# Codeshelf-0007_v02.net
KiCad netlist of a schematic drawn in EAGLE
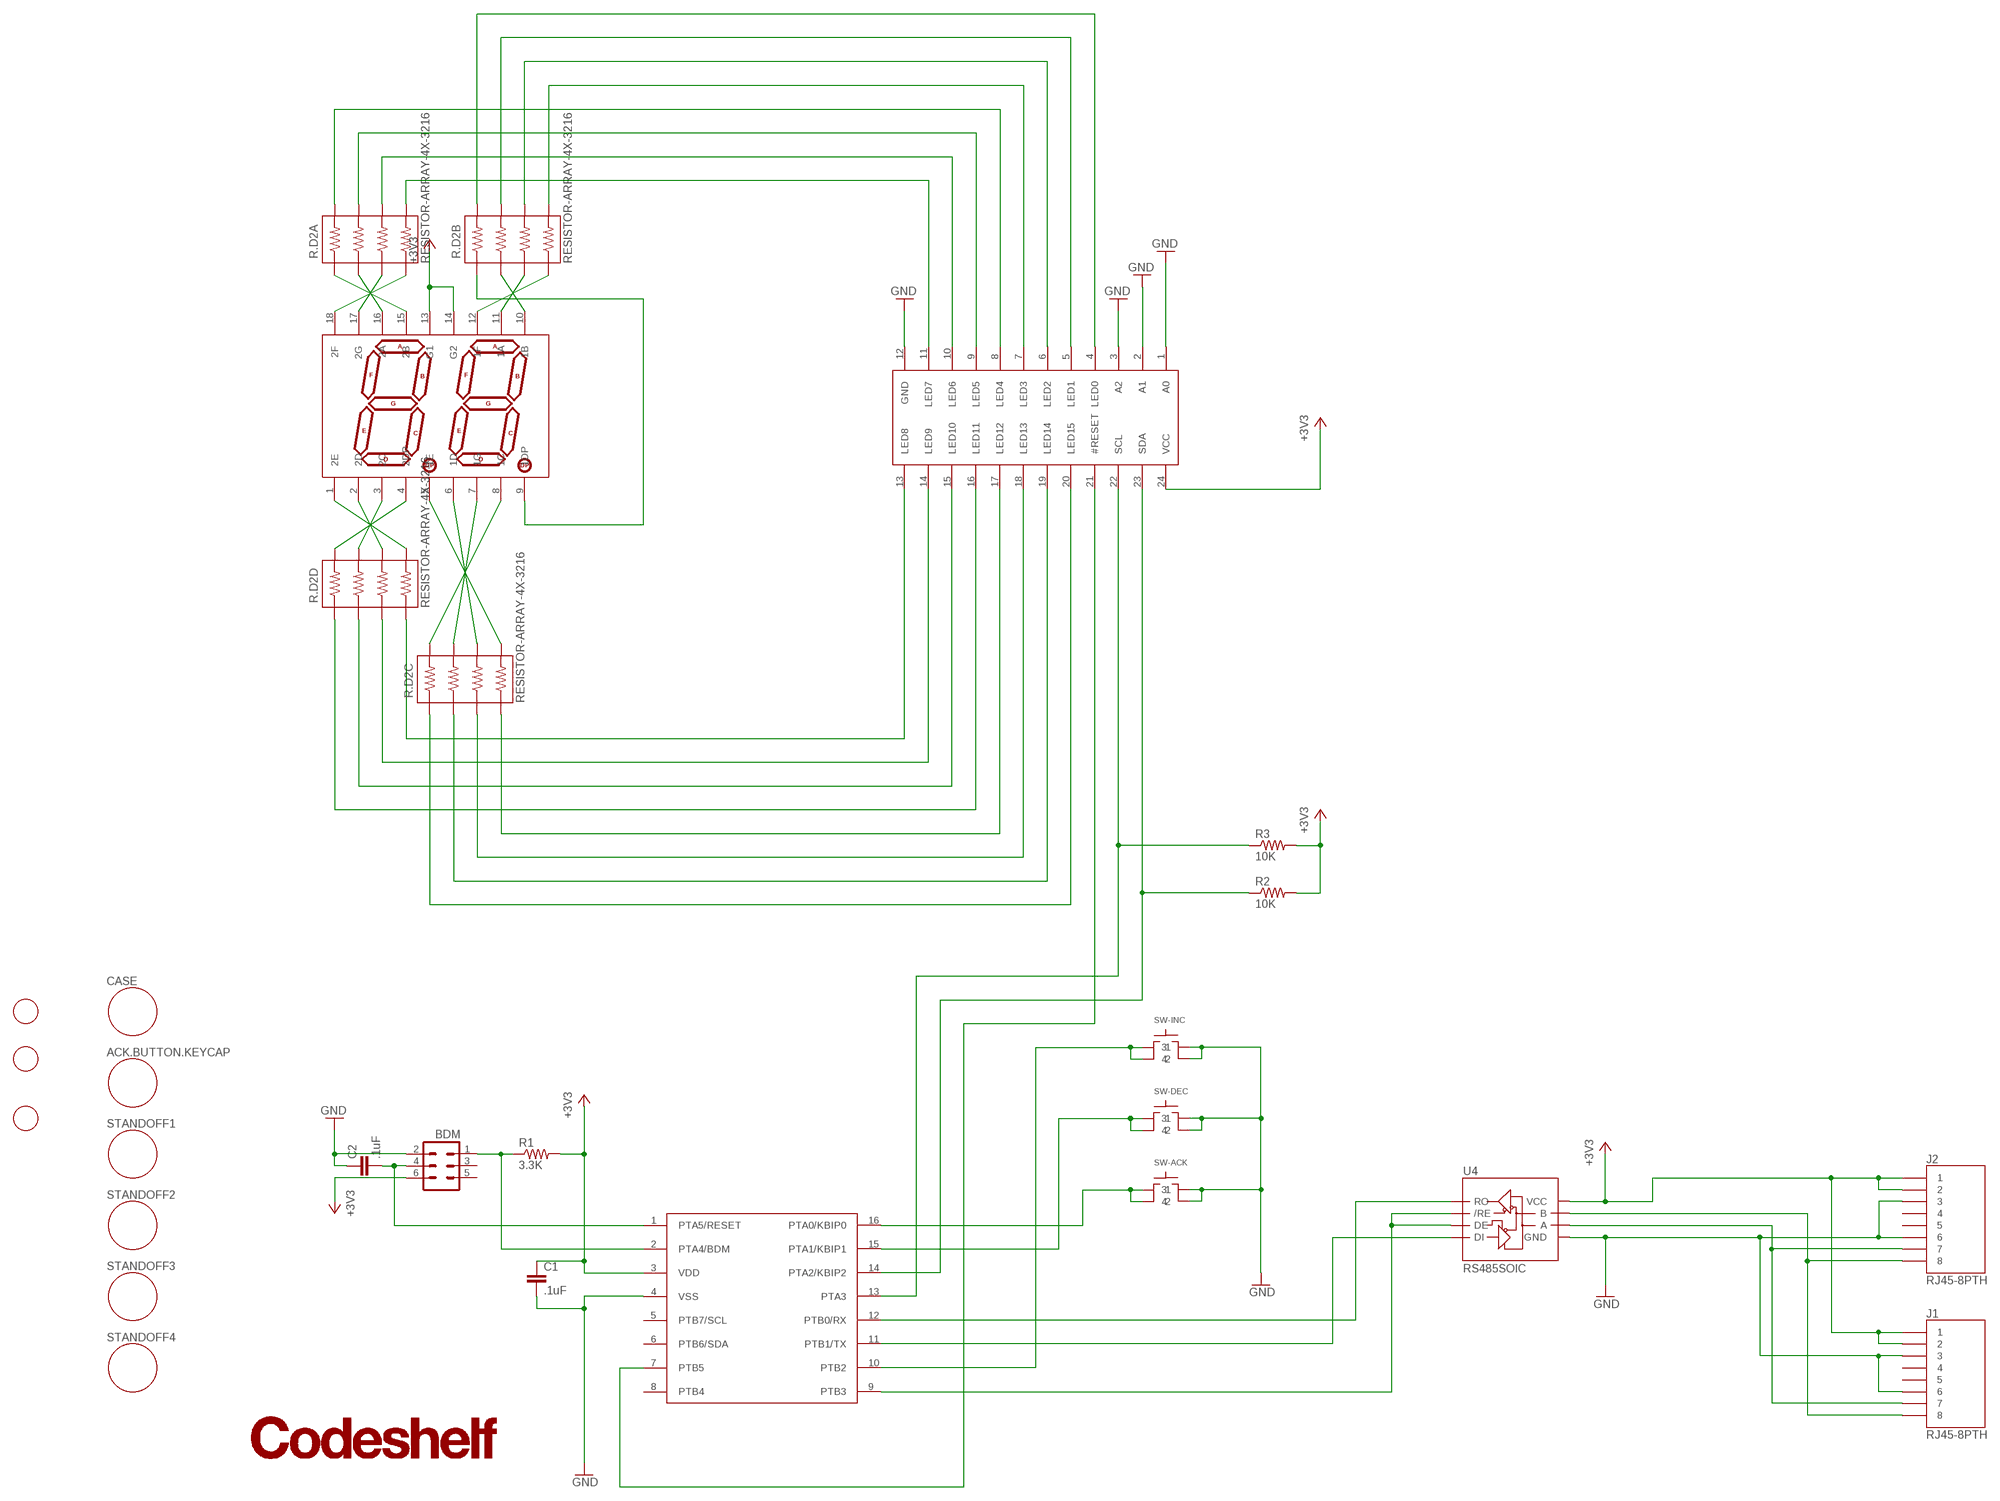
[diagram p0: schematic, sheet 1]

(export (version "E")
  (design (tool "Eeschema 10.0.6"))
  (components
    (comp (ref "ACK.BUTTON.KEYCAP")
      (value "EXTERNAL-COMPONENT")
      (footprint "eagle-import:EXTERNAL-COMPONENT")
      (libsource (lib "eagle-import") (part "EXTERNAL-COMPONENT"))
    )
    (comp (ref "BDM")
      (value "HEADER-3X2")
      (footprint "eagle-import:HEADER-3X2")
      (libsource (lib "eagle-import") (part "HEADER-3X2"))
    )
    (comp (ref "C1")
      (value ".1uF")
      (footprint "eagle-import:C0402")
      (libsource (lib "eagle-import") (part "RF-C0402"))
    )
    (comp (ref "C2")
      (value ".1uF")
      (footprint "eagle-import:C0402")
      (libsource (lib "eagle-import") (part "RF-C0402"))
    )
    (comp (ref "CASE")
      (value "EXTERNAL-COMPONENT")
      (footprint "eagle-import:EXTERNAL-COMPONENT")
      (libsource (lib "eagle-import") (part "EXTERNAL-COMPONENT"))
    )
    (comp (ref "J1")
      (value "RJ45-8PTH")
      (footprint "eagle-import:RJ45-8")
      (libsource (lib "eagle-import") (part "RJ45-8PTH"))
    )
    (comp (ref "J2")
      (value "RJ45-8PTH")
      (footprint "eagle-import:RJ45-8")
      (libsource (lib "eagle-import") (part "RJ45-8PTH"))
    )
    (comp (ref "LOGO")
      (value "CODESHELF-LOGO")
      (footprint "eagle-import:CODESHELF-LOGO")
      (libsource (lib "eagle-import") (part "CODESHELF-LOGO"))
    )
    (comp (ref "R.D2A")
      (value "RESISTOR-ARRAY-4X-3216")
      (footprint "eagle-import:3216-4X")
      (libsource (lib "eagle-import") (part "RESISTOR-ARRAY-4X-3216"))
    )
    (comp (ref "R.D2B")
      (value "RESISTOR-ARRAY-4X-3216")
      (footprint "eagle-import:3216-4X")
      (libsource (lib "eagle-import") (part "RESISTOR-ARRAY-4X-3216"))
    )
    (comp (ref "R.D2C")
      (value "RESISTOR-ARRAY-4X-3216")
      (footprint "eagle-import:3216-4X")
      (libsource (lib "eagle-import") (part "RESISTOR-ARRAY-4X-3216"))
    )
    (comp (ref "R.D2D")
      (value "RESISTOR-ARRAY-4X-3216")
      (footprint "eagle-import:3216-4X")
      (libsource (lib "eagle-import") (part "RESISTOR-ARRAY-4X-3216"))
    )
    (comp (ref "R1")
      (value "3.3K")
      (footprint "eagle-import:RF-R0402")
      (libsource (lib "eagle-import") (part "RF-R0402"))
    )
    (comp (ref "R2")
      (value "10K")
      (footprint "eagle-import:RF-R0402")
      (libsource (lib "eagle-import") (part "RF-R0402"))
    )
    (comp (ref "R3")
      (value "10K")
      (footprint "eagle-import:RF-R0402")
      (libsource (lib "eagle-import") (part "RF-R0402"))
    )
    (comp (ref "STANDOFF1")
      (value "EXTERNAL-COMPONENT")
      (footprint "eagle-import:EXTERNAL-COMPONENT")
      (libsource (lib "eagle-import") (part "EXTERNAL-COMPONENT"))
    )
    (comp (ref "STANDOFF2")
      (value "EXTERNAL-COMPONENT")
      (footprint "eagle-import:EXTERNAL-COMPONENT")
      (libsource (lib "eagle-import") (part "EXTERNAL-COMPONENT"))
    )
    (comp (ref "STANDOFF3")
      (value "EXTERNAL-COMPONENT")
      (footprint "eagle-import:EXTERNAL-COMPONENT")
      (libsource (lib "eagle-import") (part "EXTERNAL-COMPONENT"))
    )
    (comp (ref "STANDOFF4")
      (value "EXTERNAL-COMPONENT")
      (footprint "eagle-import:EXTERNAL-COMPONENT")
      (libsource (lib "eagle-import") (part "EXTERNAL-COMPONENT"))
    )
    (comp (ref "SW-ACK")
      (value "SWITCH-TACTILE-320.03E11")
      (footprint "eagle-import:SWITCH-TACTILE-320.03E11")
      (libsource (lib "eagle-import") (part "SWITCH-TACTILE-320.03E11"))
    )
    (comp (ref "SW-DEC")
      (value "SWITCH-TACTILE-FSM")
      (footprint "eagle-import:SWITCH-TACTILE-FSM")
      (libsource (lib "eagle-import") (part "SWITCH-TACTILE-FSM"))
    )
    (comp (ref "SW-INC")
      (value "SWITCH-TACTILE-FSM")
      (footprint "eagle-import:SWITCH-TACTILE-FSM")
      (libsource (lib "eagle-import") (part "SWITCH-TACTILE-FSM"))
    )
    (comp (ref "U$1")
      (value "FIDUCIAL")
      (footprint "eagle-import:FIDUCIAL_1MM")
      (libsource (lib "eagle-import") (part "FIDUCIAL"))
    )
    (comp (ref "U$2")
      (value "FIDUCIAL")
      (footprint "eagle-import:FIDUCIAL_1MM")
      (libsource (lib "eagle-import") (part "FIDUCIAL"))
    )
    (comp (ref "U$3")
      (value "FIDUCIAL")
      (footprint "eagle-import:FIDUCIAL_1MM")
      (libsource (lib "eagle-import") (part "FIDUCIAL"))
    )
    (comp (ref "U2")
      (value "MC9S08QG-DT")
      (footprint "eagle-import:TSSOP16")
      (libsource (lib "eagle-import") (part "MC9S08QG-DT"))
    )
    (comp (ref "U3")
      (value "CAT9552")
      (footprint "eagle-import:TSSOP24")
      (libsource (lib "eagle-import") (part "CAT9552"))
    )
    (comp (ref "U4")
      (value "RS485SOIC")
      (footprint "eagle-import:SO08")
      (libsource (lib "eagle-import") (part "RS485SOIC"))
    )
    (comp (ref "U7")
      (value "7SEGMENT-2DIGIT")
      (footprint "eagle-import:7SEGMENT-2DIG-.54")
      (libsource (lib "eagle-import") (part "7SEGMENT-2DIGIT"))
    )
  )
  (nets
    (net (code "1") (name "+3V3") (class "Default")
      (node (ref "BDM") (pin "6") (pinfunction "6_6") (pintype "passive"))
      (node (ref "C1") (pin "1") (pinfunction "1_1") (pintype "passive"))
      (node (ref "J1") (pin "1") (pinfunction "1_1") (pintype "bidirectional"))
      (node (ref "J1") (pin "2") (pinfunction "2_2") (pintype "bidirectional"))
      (node (ref "J2") (pin "1") (pinfunction "1_1") (pintype "bidirectional"))
      (node (ref "J2") (pin "2") (pinfunction "2_2") (pintype "bidirectional"))
      (node (ref "R1") (pin "2") (pinfunction "2_2") (pintype "passive"))
      (node (ref "R2") (pin "2") (pinfunction "2_2") (pintype "passive"))
      (node (ref "R3") (pin "2") (pinfunction "2_2") (pintype "passive"))
      (node (ref "U2") (pin "3") (pinfunction "VDD_3") (pintype "bidirectional"))
      (node (ref "U3") (pin "24") (pinfunction "VCC_24") (pintype "bidirectional"))
      (node (ref "U4") (pin "8") (pinfunction "VCC_8") (pintype "bidirectional"))
      (node (ref "U7") (pin "13") (pinfunction "G1_13") (pintype "bidirectional"))
      (node (ref "U7") (pin "14") (pinfunction "G2_14") (pintype "bidirectional"))
    )
    (net (code "2") (name "GND") (class "Default")
      (node (ref "BDM") (pin "2") (pinfunction "2_2") (pintype "passive"))
      (node (ref "C1") (pin "2") (pinfunction "2_2") (pintype "passive"))
      (node (ref "C2") (pin "1") (pinfunction "1_1") (pintype "passive"))
      (node (ref "J1") (pin "3") (pinfunction "3_3") (pintype "bidirectional"))
      (node (ref "J1") (pin "6") (pinfunction "6_6") (pintype "bidirectional"))
      (node (ref "J2") (pin "3") (pinfunction "3_3") (pintype "bidirectional"))
      (node (ref "J2") (pin "6") (pinfunction "6_6") (pintype "bidirectional"))
      (node (ref "SW-ACK") (pin "P$3") (pinfunction "3_P$3") (pintype "input"))
      (node (ref "SW-ACK") (pin "P$4") (pinfunction "4_P$4") (pintype "input"))
      (node (ref "SW-DEC") (pin "P$3") (pinfunction "3_P$3") (pintype "input"))
      (node (ref "SW-DEC") (pin "P$4") (pinfunction "4_P$4") (pintype "input"))
      (node (ref "SW-INC") (pin "P$3") (pinfunction "3_P$3") (pintype "input"))
      (node (ref "SW-INC") (pin "P$4") (pinfunction "4_P$4") (pintype "input"))
      (node (ref "U2") (pin "4") (pinfunction "VSS_4") (pintype "bidirectional"))
      (node (ref "U3") (pin "1") (pinfunction "A0_1") (pintype "bidirectional"))
      (node (ref "U3") (pin "12") (pinfunction "GND_12") (pintype "bidirectional"))
      (node (ref "U3") (pin "2") (pinfunction "A1_2") (pintype "bidirectional"))
      (node (ref "U3") (pin "3") (pinfunction "A2_3") (pintype "bidirectional"))
      (node (ref "U4") (pin "5") (pinfunction "GND_5") (pintype "bidirectional"))
    )
    (net (code "3") (name "Net-(R.D2A-1A)") (class "Default")
      (node (ref "R.D2A") (pin "1") (pinfunction "1A_1") (pintype "passive"))
      (node (ref "U7") (pin "15") (pinfunction "2B_15") (pintype "bidirectional"))
    )
    (net (code "4") (name "Net-(R.D2A-1B)") (class "Default")
      (node (ref "R.D2A") (pin "8") (pinfunction "1B_8") (pintype "passive"))
      (node (ref "U3") (pin "8") (pinfunction "LED4_8") (pintype "bidirectional"))
    )
    (net (code "5") (name "Net-(R.D2A-2A)") (class "Default")
      (node (ref "R.D2A") (pin "2") (pinfunction "2A_2") (pintype "passive"))
      (node (ref "U7") (pin "16") (pinfunction "2A_16") (pintype "bidirectional"))
    )
    (net (code "6") (name "Net-(R.D2A-2B)") (class "Default")
      (node (ref "R.D2A") (pin "7") (pinfunction "2B_7") (pintype "passive"))
      (node (ref "U3") (pin "9") (pinfunction "LED5_9") (pintype "bidirectional"))
    )
    (net (code "7") (name "Net-(R.D2A-3A)") (class "Default")
      (node (ref "R.D2A") (pin "3") (pinfunction "3A_3") (pintype "passive"))
      (node (ref "U7") (pin "17") (pinfunction "2G_17") (pintype "bidirectional"))
    )
    (net (code "8") (name "Net-(R.D2A-3B)") (class "Default")
      (node (ref "R.D2A") (pin "6") (pinfunction "3B_6") (pintype "passive"))
      (node (ref "U3") (pin "10") (pinfunction "LED6_10") (pintype "bidirectional"))
    )
    (net (code "9") (name "Net-(R.D2A-4A)") (class "Default")
      (node (ref "R.D2A") (pin "4") (pinfunction "4A_4") (pintype "passive"))
      (node (ref "U7") (pin "18") (pinfunction "2F_18") (pintype "bidirectional"))
    )
    (net (code "10") (name "Net-(R.D2A-4B)") (class "Default")
      (node (ref "R.D2A") (pin "5") (pinfunction "4B_5") (pintype "passive"))
      (node (ref "U3") (pin "11") (pinfunction "LED7_11") (pintype "bidirectional"))
    )
    (net (code "11") (name "Net-(R.D2B-1A)") (class "Default")
      (node (ref "R.D2B") (pin "1") (pinfunction "1A_1") (pintype "passive"))
      (node (ref "U7") (pin "9") (pinfunction "1DP_9") (pintype "bidirectional"))
    )
    (net (code "12") (name "Net-(R.D2B-1B)") (class "Default")
      (node (ref "R.D2B") (pin "8") (pinfunction "1B_8") (pintype "passive"))
      (node (ref "U3") (pin "4") (pinfunction "LED0_4") (pintype "bidirectional"))
    )
    (net (code "13") (name "Net-(R.D2B-2A)") (class "Default")
      (node (ref "R.D2B") (pin "2") (pinfunction "2A_2") (pintype "passive"))
      (node (ref "U7") (pin "10") (pinfunction "1B_10") (pintype "bidirectional"))
    )
    (net (code "14") (name "Net-(R.D2B-2B)") (class "Default")
      (node (ref "R.D2B") (pin "7") (pinfunction "2B_7") (pintype "passive"))
      (node (ref "U3") (pin "5") (pinfunction "LED1_5") (pintype "bidirectional"))
    )
    (net (code "15") (name "Net-(R.D2B-3A)") (class "Default")
      (node (ref "R.D2B") (pin "3") (pinfunction "3A_3") (pintype "passive"))
      (node (ref "U7") (pin "11") (pinfunction "1A_11") (pintype "bidirectional"))
    )
    (net (code "16") (name "Net-(R.D2B-3B)") (class "Default")
      (node (ref "R.D2B") (pin "6") (pinfunction "3B_6") (pintype "passive"))
      (node (ref "U3") (pin "6") (pinfunction "LED2_6") (pintype "bidirectional"))
    )
    (net (code "17") (name "Net-(R.D2B-4A)") (class "Default")
      (node (ref "R.D2B") (pin "4") (pinfunction "4A_4") (pintype "passive"))
      (node (ref "U7") (pin "12") (pinfunction "1F_12") (pintype "bidirectional"))
    )
    (net (code "18") (name "Net-(R.D2B-4B)") (class "Default")
      (node (ref "R.D2B") (pin "5") (pinfunction "4B_5") (pintype "passive"))
      (node (ref "U3") (pin "7") (pinfunction "LED3_7") (pintype "bidirectional"))
    )
    (net (code "19") (name "Net-(R.D2C-1A)") (class "Default")
      (node (ref "R.D2C") (pin "1") (pinfunction "1A_1") (pintype "passive"))
      (node (ref "U3") (pin "20") (pinfunction "LED15_20") (pintype "bidirectional"))
    )
    (net (code "20") (name "Net-(R.D2C-1B)") (class "Default")
      (node (ref "R.D2C") (pin "8") (pinfunction "1B_8") (pintype "passive"))
      (node (ref "U7") (pin "8") (pinfunction "1C_8") (pintype "bidirectional"))
    )
    (net (code "21") (name "Net-(R.D2C-2A)") (class "Default")
      (node (ref "R.D2C") (pin "2") (pinfunction "2A_2") (pintype "passive"))
      (node (ref "U3") (pin "19") (pinfunction "LED14_19") (pintype "bidirectional"))
    )
    (net (code "22") (name "Net-(R.D2C-2B)") (class "Default")
      (node (ref "R.D2C") (pin "7") (pinfunction "2B_7") (pintype "passive"))
      (node (ref "U7") (pin "7") (pinfunction "1G_7") (pintype "bidirectional"))
    )
    (net (code "23") (name "Net-(R.D2C-3A)") (class "Default")
      (node (ref "R.D2C") (pin "3") (pinfunction "3A_3") (pintype "passive"))
      (node (ref "U3") (pin "18") (pinfunction "LED13_18") (pintype "bidirectional"))
    )
    (net (code "24") (name "Net-(R.D2C-3B)") (class "Default")
      (node (ref "R.D2C") (pin "6") (pinfunction "3B_6") (pintype "passive"))
      (node (ref "U7") (pin "6") (pinfunction "1D_6") (pintype "bidirectional"))
    )
    (net (code "25") (name "Net-(R.D2C-4A)") (class "Default")
      (node (ref "R.D2C") (pin "4") (pinfunction "4A_4") (pintype "passive"))
      (node (ref "U3") (pin "17") (pinfunction "LED12_17") (pintype "bidirectional"))
    )
    (net (code "26") (name "Net-(R.D2C-4B)") (class "Default")
      (node (ref "R.D2C") (pin "5") (pinfunction "4B_5") (pintype "passive"))
      (node (ref "U7") (pin "5") (pinfunction "1E_5") (pintype "bidirectional"))
    )
    (net (code "27") (name "Net-(R.D2D-1A)") (class "Default")
      (node (ref "R.D2D") (pin "1") (pinfunction "1A_1") (pintype "passive"))
      (node (ref "U3") (pin "16") (pinfunction "LED11_16") (pintype "bidirectional"))
    )
    (net (code "28") (name "Net-(R.D2D-1B)") (class "Default")
      (node (ref "R.D2D") (pin "8") (pinfunction "1B_8") (pintype "passive"))
      (node (ref "U7") (pin "4") (pinfunction "2DP_4") (pintype "bidirectional"))
    )
    (net (code "29") (name "Net-(R.D2D-2A)") (class "Default")
      (node (ref "R.D2D") (pin "2") (pinfunction "2A_2") (pintype "passive"))
      (node (ref "U3") (pin "15") (pinfunction "LED10_15") (pintype "bidirectional"))
    )
    (net (code "30") (name "Net-(R.D2D-2B)") (class "Default")
      (node (ref "R.D2D") (pin "7") (pinfunction "2B_7") (pintype "passive"))
      (node (ref "U7") (pin "3") (pinfunction "2C_3") (pintype "bidirectional"))
    )
    (net (code "31") (name "Net-(R.D2D-3A)") (class "Default")
      (node (ref "R.D2D") (pin "3") (pinfunction "3A_3") (pintype "passive"))
      (node (ref "U3") (pin "14") (pinfunction "LED9_14") (pintype "bidirectional"))
    )
    (net (code "32") (name "Net-(R.D2D-3B)") (class "Default")
      (node (ref "R.D2D") (pin "6") (pinfunction "3B_6") (pintype "passive"))
      (node (ref "U7") (pin "2") (pinfunction "2D_2") (pintype "bidirectional"))
    )
    (net (code "33") (name "Net-(R.D2D-4A)") (class "Default")
      (node (ref "R.D2D") (pin "4") (pinfunction "4A_4") (pintype "passive"))
      (node (ref "U3") (pin "13") (pinfunction "LED8_13") (pintype "bidirectional"))
    )
    (net (code "34") (name "Net-(R.D2D-4B)") (class "Default")
      (node (ref "R.D2D") (pin "5") (pinfunction "4B_5") (pintype "passive"))
      (node (ref "U7") (pin "1") (pinfunction "2E_1") (pintype "bidirectional"))
    )
    (net (code "35") (name "Net-(SW-ACK-1)") (class "Default")
      (node (ref "SW-ACK") (pin "P$1") (pinfunction "1_P$1") (pintype "input"))
      (node (ref "SW-ACK") (pin "P$2") (pinfunction "2_P$2") (pintype "input"))
      (node (ref "U2") (pin "16") (pinfunction "PTA0/KBIP0_16") (pintype "bidirectional"))
    )
    (net (code "36") (name "Net-(SW-DEC-1)") (class "Default")
      (node (ref "SW-DEC") (pin "P$1") (pinfunction "1_P$1") (pintype "input"))
      (node (ref "SW-DEC") (pin "P$2") (pinfunction "2_P$2") (pintype "input"))
      (node (ref "U2") (pin "15") (pinfunction "PTA1/KBIP1_15") (pintype "bidirectional"))
    )
    (net (code "37") (name "Net-(SW-INC-1)") (class "Default")
      (node (ref "SW-INC") (pin "P$1") (pinfunction "1_P$1") (pintype "input"))
      (node (ref "SW-INC") (pin "P$2") (pinfunction "2_P$2") (pintype "input"))
      (node (ref "U2") (pin "10") (pinfunction "PTB2_10") (pintype "bidirectional"))
    )
    (net (code "38") (name "Net-(U2-PTA2{slash}KBIP2)") (class "Default")
      (node (ref "R2") (pin "1") (pinfunction "1_1") (pintype "passive"))
      (node (ref "U2") (pin "14") (pinfunction "PTA2/KBIP2_14") (pintype "bidirectional"))
      (node (ref "U3") (pin "23") (pinfunction "SDA_23") (pintype "bidirectional"))
    )
    (net (code "39") (name "Net-(U2-PTA3)") (class "Default")
      (node (ref "R3") (pin "1") (pinfunction "1_1") (pintype "passive"))
      (node (ref "U2") (pin "13") (pinfunction "PTA3_13") (pintype "bidirectional"))
      (node (ref "U3") (pin "22") (pinfunction "SCL_22") (pintype "bidirectional"))
    )
    (net (code "40") (name "Net-(U2-PTA4{slash}BDM)") (class "Default")
      (node (ref "BDM") (pin "1") (pinfunction "1_1") (pintype "passive"))
      (node (ref "R1") (pin "1") (pinfunction "1_1") (pintype "passive"))
      (node (ref "U2") (pin "2") (pinfunction "PTA4/BDM_2") (pintype "bidirectional"))
    )
    (net (code "41") (name "Net-(U2-PTA5{slash}RESET)") (class "Default")
      (node (ref "BDM") (pin "4") (pinfunction "4_4") (pintype "passive"))
      (node (ref "C2") (pin "2") (pinfunction "2_2") (pintype "passive"))
      (node (ref "U2") (pin "1") (pinfunction "PTA5/RESET_1") (pintype "bidirectional"))
    )
    (net (code "42") (name "Net-(U2-PTB0{slash}RX)") (class "Default")
      (node (ref "U2") (pin "12") (pinfunction "PTB0/RX_12") (pintype "bidirectional"))
      (node (ref "U4") (pin "1") (pinfunction "RO_1") (pintype "bidirectional"))
    )
    (net (code "43") (name "Net-(U2-PTB1{slash}TX)") (class "Default")
      (node (ref "U2") (pin "11") (pinfunction "PTB1/TX_11") (pintype "bidirectional"))
      (node (ref "U4") (pin "4") (pinfunction "DI_4") (pintype "bidirectional"))
    )
    (net (code "44") (name "Net-(U2-PTB3)") (class "Default")
      (node (ref "U2") (pin "9") (pinfunction "PTB3_9") (pintype "bidirectional"))
      (node (ref "U4") (pin "2") (pinfunction "/RE_2") (pintype "bidirectional"))
      (node (ref "U4") (pin "3") (pinfunction "DE_3") (pintype "bidirectional"))
    )
    (net (code "45") (name "Net-(U2-PTB5)") (class "Default")
      (node (ref "U2") (pin "7") (pinfunction "PTB5_7") (pintype "bidirectional"))
      (node (ref "U3") (pin "21") (pinfunction "#RESET_21") (pintype "bidirectional"))
    )
    (net (code "46") (name "Net-(U4-A)") (class "Default")
      (node (ref "J1") (pin "7") (pinfunction "7_7") (pintype "bidirectional"))
      (node (ref "J2") (pin "7") (pinfunction "7_7") (pintype "bidirectional"))
      (node (ref "U4") (pin "6") (pinfunction "A_6") (pintype "bidirectional"))
    )
    (net (code "47") (name "Net-(U4-B)") (class "Default")
      (node (ref "J1") (pin "8") (pinfunction "8_8") (pintype "bidirectional"))
      (node (ref "J2") (pin "8") (pinfunction "8_8") (pintype "bidirectional"))
      (node (ref "U4") (pin "7") (pinfunction "B_7") (pintype "bidirectional"))
    )
    (net (code "48") (name "unconnected-(BDM-Pad3)") (class "Default")
      (node (ref "BDM") (pin "3") (pinfunction "3_3") (pintype "passive"))
    )
    (net (code "49") (name "unconnected-(BDM-Pad5)") (class "Default")
      (node (ref "BDM") (pin "5") (pinfunction "5_5") (pintype "passive"))
    )
    (net (code "50") (name "unconnected-(J1-Pad4)") (class "Default")
      (node (ref "J1") (pin "4") (pinfunction "4_4") (pintype "bidirectional"))
    )
    (net (code "51") (name "unconnected-(J1-Pad5)") (class "Default")
      (node (ref "J1") (pin "5") (pinfunction "5_5") (pintype "bidirectional"))
    )
    (net (code "52") (name "unconnected-(J2-Pad4)") (class "Default")
      (node (ref "J2") (pin "4") (pinfunction "4_4") (pintype "bidirectional"))
    )
    (net (code "53") (name "unconnected-(J2-Pad5)") (class "Default")
      (node (ref "J2") (pin "5") (pinfunction "5_5") (pintype "bidirectional"))
    )
    (net (code "54") (name "unconnected-(U2-PTB4-Pad8)") (class "Default")
      (node (ref "U2") (pin "8") (pinfunction "PTB4_8") (pintype "bidirectional"))
    )
    (net (code "55") (name "unconnected-(U2-PTB6{slash}SDA-Pad6)") (class "Default")
      (node (ref "U2") (pin "6") (pinfunction "PTB6/SDA_6") (pintype "bidirectional"))
    )
    (net (code "56") (name "unconnected-(U2-PTB7{slash}SCL-Pad5)") (class "Default")
      (node (ref "U2") (pin "5") (pinfunction "PTB7/SCL_5") (pintype "bidirectional"))
    )
  )
)
